# Modelo-1.net
KiCad netlist of a schematic drawn in Altium Designer
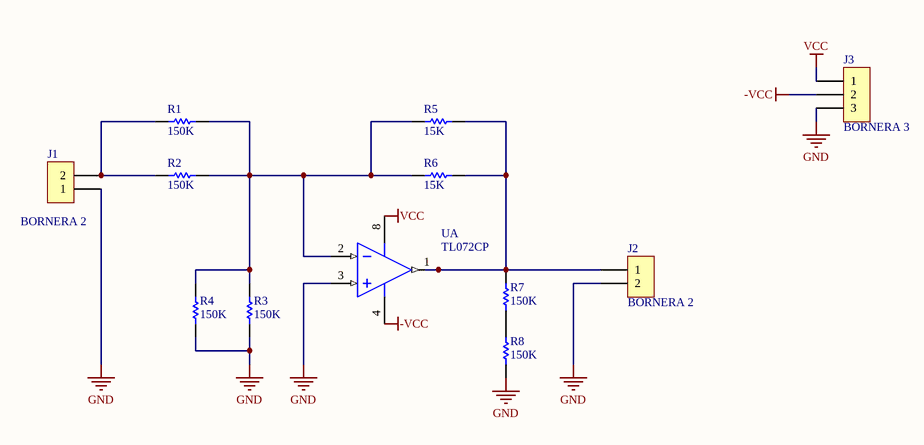
[diagram p0: Modelo-1.SchDoc]

(export (version "E")
  (design (tool "Eeschema 10.0.6"))
  (components
    (comp (ref "J1") (value "BORNERA 2") (footprint "BORNERA2") (libsource (lib "") (part "BORNERA 2_1")))
    (comp (ref "J2")
      (value "BORNERA 2")
      (footprint "BORNERA2")
      (libsource (lib "LIBEBAL") (part "BORNERA 2"))
    )
    (comp (ref "J3")
      (value "BORNERA 3")
      (footprint "BORNERA3")
      (libsource (lib "LIBEBAL") (part "BORNERA 3"))
    )
    (comp (ref "R1") (value "150K") (footprint "RES400") (libsource (lib "LIBEBAL") (part "RES")))
    (comp (ref "R2") (value "150K") (footprint "RES400") (libsource (lib "LIBEBAL") (part "RES")))
    (comp (ref "R3") (value "150K") (footprint "RES400") (libsource (lib "LIBEBAL") (part "RES")))
    (comp (ref "R4") (value "150K") (footprint "RES400") (libsource (lib "LIBEBAL") (part "RES")))
    (comp (ref "R5") (value "15K") (footprint "RES400") (libsource (lib "LIBEBAL") (part "RES")))
    (comp (ref "R6") (value "15K") (footprint "RES400") (libsource (lib "LIBEBAL") (part "RES")))
    (comp (ref "R7") (value "150K") (footprint "RES400") (libsource (lib "LIBEBAL") (part "RES")))
    (comp (ref "R8") (value "150K") (footprint "RES400") (libsource (lib "LIBEBAL") (part "RES")))
    (comp (ref "U")
      (value "TL072CP")
      (footprint "TI-P8")
      (fields (field (name "MANUFACTURER") "Texas Instruments"))
      (libsource (lib "TI Amplifiers and Linear Operational Amplifier General Purpose") (part "TL072CP"))
    )
  )
  (nets
    (net (code "1") (name "-VCC") (class "Default")
      (node (ref "J3") (pin "2") (pinfunction "2_2") (pintype "passive"))
      (node (ref "U") (pin "4") (pinfunction "VCC-_4") (pintype "power_in"))
    )
    (net (code "2") (name "GND") (class "Default")
      (node (ref "J1") (pin "1") (pinfunction "1_1") (pintype "passive"))
      (node (ref "J2") (pin "2") (pinfunction "2_2") (pintype "passive"))
      (node (ref "J3") (pin "3") (pinfunction "3_3") (pintype "passive"))
      (node (ref "R3") (pin "1") (pinfunction "1_1") (pintype "passive"))
      (node (ref "R4") (pin "1") (pinfunction "1_1") (pintype "passive"))
      (node (ref "R8") (pin "1") (pinfunction "1_1") (pintype "passive"))
      (node (ref "U") (pin "3") (pinfunction "IN1+_3") (pintype "input"))
    )
    (net (code "3") (name "Net-(J1-Pad2)") (class "Default")
      (node (ref "J1") (pin "2") (pinfunction "2_2") (pintype "passive"))
      (node (ref "R1") (pin "1") (pinfunction "1_1") (pintype "passive"))
      (node (ref "R2") (pin "1") (pinfunction "1_1") (pintype "passive"))
    )
    (net (code "4") (name "Net-(R7-Pad2)") (class "Default")
      (node (ref "R7") (pin "2") (pinfunction "2_2") (pintype "passive"))
      (node (ref "R8") (pin "2") (pinfunction "2_2") (pintype "passive"))
    )
    (net (code "5") (name "Net-(UA-IN1-)") (class "Default")
      (node (ref "R1") (pin "2") (pinfunction "2_2") (pintype "passive"))
      (node (ref "R2") (pin "2") (pinfunction "2_2") (pintype "passive"))
      (node (ref "R3") (pin "2") (pinfunction "2_2") (pintype "passive"))
      (node (ref "R4") (pin "2") (pinfunction "2_2") (pintype "passive"))
      (node (ref "R5") (pin "1") (pinfunction "1_1") (pintype "passive"))
      (node (ref "R6") (pin "2") (pinfunction "2_2") (pintype "passive"))
      (node (ref "U") (pin "2") (pinfunction "IN1-_2") (pintype "input"))
    )
    (net (code "6") (name "Net-(UA-OUT1)") (class "Default")
      (node (ref "J2") (pin "1") (pinfunction "1_1") (pintype "passive"))
      (node (ref "R5") (pin "2") (pinfunction "2_2") (pintype "passive"))
      (node (ref "R6") (pin "1") (pinfunction "1_1") (pintype "passive"))
      (node (ref "R7") (pin "1") (pinfunction "1_1") (pintype "passive"))
      (node (ref "U") (pin "1") (pinfunction "OUT1_1") (pintype "output"))
    )
    (net (code "7") (name "VCC") (class "Default")
      (node (ref "J3") (pin "1") (pinfunction "1_1") (pintype "passive"))
      (node (ref "U") (pin "8") (pinfunction "VCC+_8") (pintype "power_in"))
    )
  )
)
